# Power_Supply_for_CPU_Blocks.net
KiCad netlist of a schematic drawn in Altium Designer
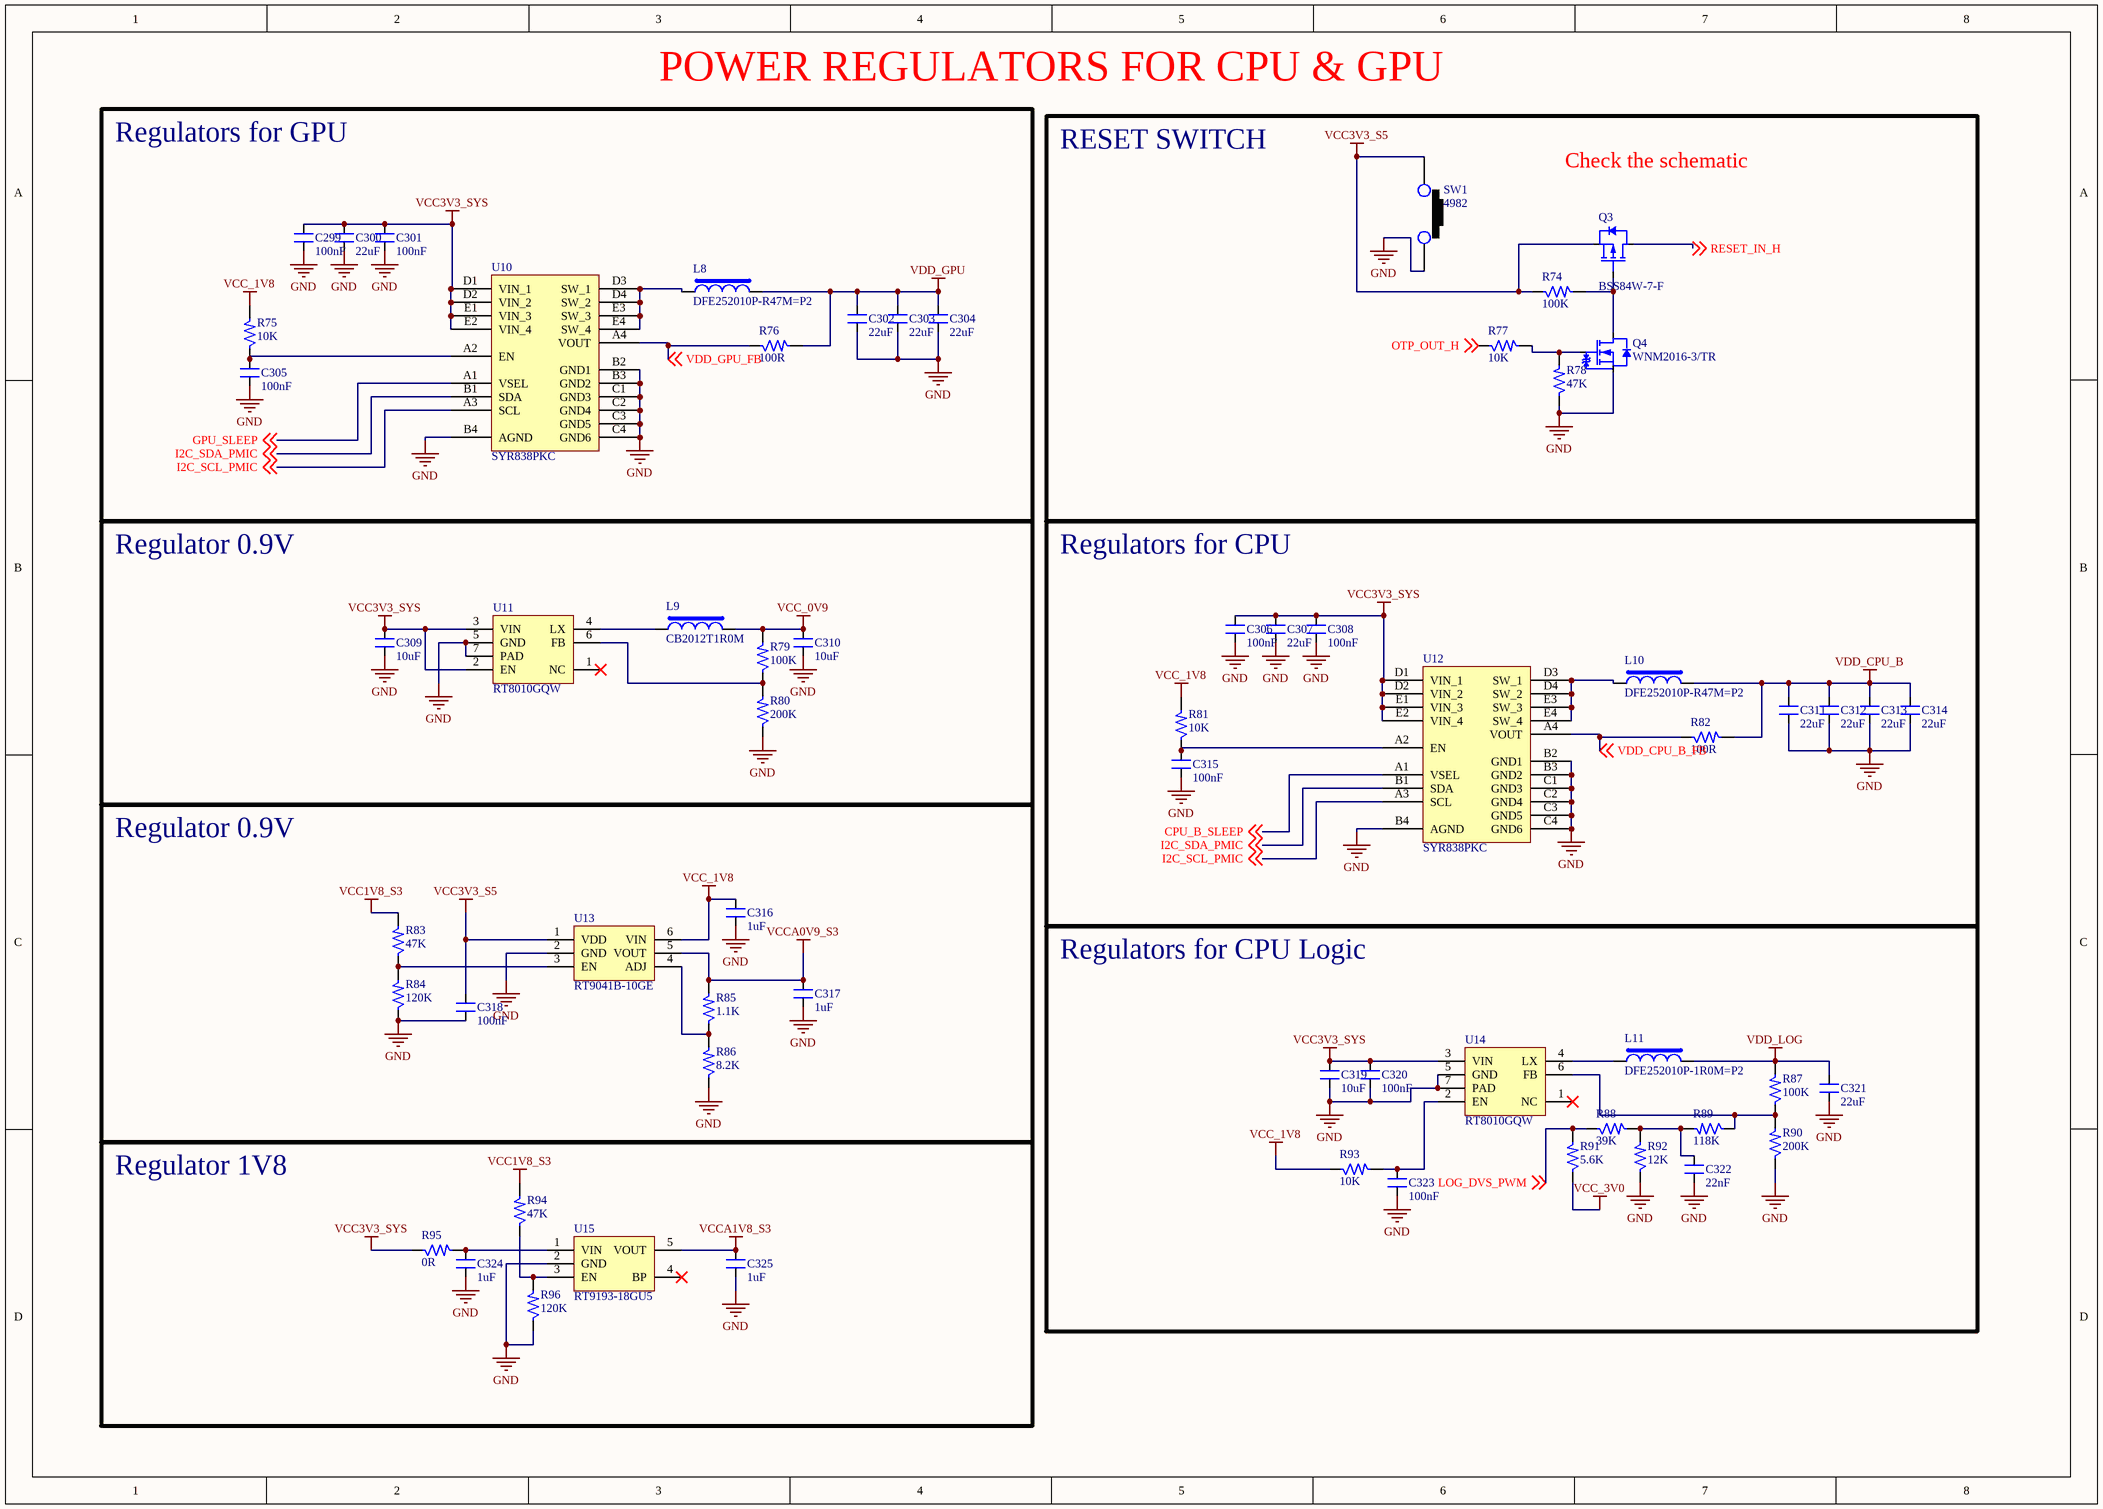
[diagram p0: Power Supply for CPU Blocks.SchDoc]

(export (version "E")
  (design (tool "Eeschema 10.0.6"))
  (components
    (comp (ref "C299")
      (value "100nF")
      (footprint "CAP_0603")
      (description "0.1µF ±10% 10V Ceramic Capacitor X7R 0603 (1608 Metric)")
      (fields
        (field (name "MANUFACTURER") "Yageo")
        (field (name "MANUFACTURER PART NUMBER") "CC0603KRX7R6BB104")
      )
      (libsource (lib "RK3399 _Module_Schlib") (part "CAP_100nF-10V-5%-0603"))
    )
    (comp (ref "C300")
      (value "22uF")
      (footprint "CAP_0603")
      (description "22µF ±20% 10V Ceramic Capacitor X5R 0603 (1608 Metric)")
      (fields
        (field (name "MANUFACTURER") "Murata Electronics")
        (field (name "MANUFACTURER PART NUMBER") "GRM188R61A226ME15D")
      )
      (libsource (lib "RK3399 _Module_Schlib") (part "CAP_22uF-10V-20%-0603"))
    )
    (comp (ref "C301")
      (value "100nF")
      (footprint "CAP_0603")
      (description "0.1µF ±10% 10V Ceramic Capacitor X7R 0603 (1608 Metric)")
      (fields
        (field (name "MANUFACTURER") "Yageo")
        (field (name "MANUFACTURER PART NUMBER") "CC0603KRX7R6BB104")
      )
      (libsource (lib "RK3399 _Module_Schlib") (part "CAP_100nF-10V-5%-0603"))
    )
    (comp (ref "C302")
      (value "22uF")
      (footprint "CAP_0805")
      (description "22µF ±20% 25V Ceramic Capacitor X5R 0805 (2012 Metric)")
      (fields
        (field (name "MANUFACTURER") "Murata Electronics")
        (field (name "MANUFACTURER PART NUMBER") "GRM21BR61E226ME44K")
      )
      (libsource (lib "RK3399 _Module_Schlib") (part "CAP_22uF-25V-20%-0805"))
    )
    (comp (ref "C303")
      (value "22uF")
      (footprint "CAP_0805")
      (description "22µF ±20% 25V Ceramic Capacitor X5R 0805 (2012 Metric)")
      (fields
        (field (name "MANUFACTURER") "Murata Electronics")
        (field (name "MANUFACTURER PART NUMBER") "GRM21BR61E226ME44K")
      )
      (libsource (lib "RK3399 _Module_Schlib") (part "CAP_22uF-25V-20%-0805"))
    )
    (comp (ref "C304")
      (value "22uF")
      (footprint "CAP_0805")
      (description "22µF ±20% 25V Ceramic Capacitor X5R 0805 (2012 Metric)")
      (fields
        (field (name "MANUFACTURER") "Murata Electronics")
        (field (name "MANUFACTURER PART NUMBER") "GRM21BR61E226ME44K")
      )
      (libsource (lib "RK3399 _Module_Schlib") (part "CAP_22uF-25V-20%-0805"))
    )
    (comp (ref "C305")
      (value "100nF")
      (footprint "CAP_0603")
      (description "0.1µF ±10% 10V Ceramic Capacitor X7R 0603 (1608 Metric)")
      (fields
        (field (name "MANUFACTURER") "Yageo")
        (field (name "MANUFACTURER PART NUMBER") "CC0603KRX7R6BB104")
      )
      (libsource (lib "RK3399 _Module_Schlib") (part "CAP_100nF-10V-5%-0603"))
    )
    (comp (ref "C306")
      (value "100nF")
      (footprint "CAP_0603")
      (description "0.1µF ±10% 10V Ceramic Capacitor X7R 0603 (1608 Metric)")
      (fields
        (field (name "MANUFACTURER") "Yageo")
        (field (name "MANUFACTURER PART NUMBER") "CC0603KRX7R6BB104")
      )
      (libsource (lib "RK3399 _Module_Schlib") (part "CAP_100nF-10V-5%-0603"))
    )
    (comp (ref "C307")
      (value "22uF")
      (footprint "CAP_0603")
      (description "22µF ±20% 10V Ceramic Capacitor X5R 0603 (1608 Metric)")
      (fields
        (field (name "MANUFACTURER") "Murata Electronics")
        (field (name "MANUFACTURER PART NUMBER") "GRM188R61A226ME15D")
      )
      (libsource (lib "RK3399 _Module_Schlib") (part "CAP_22uF-10V-20%-0603"))
    )
    (comp (ref "C308")
      (value "100nF")
      (footprint "CAP_0603")
      (description "0.1µF ±10% 10V Ceramic Capacitor X7R 0603 (1608 Metric)")
      (fields
        (field (name "MANUFACTURER") "Yageo")
        (field (name "MANUFACTURER PART NUMBER") "CC0603KRX7R6BB104")
      )
      (libsource (lib "RK3399 _Module_Schlib") (part "CAP_100nF-10V-5%-0603"))
    )
    (comp (ref "C309")
      (value "10uF")
      (footprint "CAP_0603")
      (description "10µF ±10% 10V Ceramic Capacitor X5R 0603 (1608 Metric)")
      (fields
        (field (name "MANUFACTURER PART NUMBER") "GRM188R61A106KE69J")
        (field (name "MANUFACTURER") "Murata Electronics")
      )
      (libsource (lib "RK3399 _Module_Schlib") (part "CAP_10uF-10V-10%-0603"))
    )
    (comp (ref "C310")
      (value "10uF")
      (footprint "CAP_0603")
      (description "10µF ±10% 10V Ceramic Capacitor X5R 0603 (1608 Metric)")
      (fields
        (field (name "MANUFACTURER PART NUMBER") "GRM188R61A106KE69J")
        (field (name "MANUFACTURER") "Murata Electronics")
      )
      (libsource (lib "RK3399 _Module_Schlib") (part "CAP_10uF-10V-10%-0603"))
    )
    (comp (ref "C311")
      (value "22uF")
      (footprint "CAP_0805")
      (description "22µF ±20% 25V Ceramic Capacitor X5R 0805 (2012 Metric)")
      (fields
        (field (name "MANUFACTURER") "Murata Electronics")
        (field (name "MANUFACTURER PART NUMBER") "GRM21BR61E226ME44K")
      )
      (libsource (lib "RK3399 _Module_Schlib") (part "CAP_22uF-25V-20%-0805"))
    )
    (comp (ref "C312")
      (value "22uF")
      (footprint "CAP_0805")
      (description "22µF ±20% 25V Ceramic Capacitor X5R 0805 (2012 Metric)")
      (fields
        (field (name "MANUFACTURER") "Murata Electronics")
        (field (name "MANUFACTURER PART NUMBER") "GRM21BR61E226ME44K")
      )
      (libsource (lib "RK3399 _Module_Schlib") (part "CAP_22uF-25V-20%-0805"))
    )
    (comp (ref "C313")
      (value "22uF")
      (footprint "CAP_0805")
      (description "22µF ±20% 25V Ceramic Capacitor X5R 0805 (2012 Metric)")
      (fields
        (field (name "MANUFACTURER") "Murata Electronics")
        (field (name "MANUFACTURER PART NUMBER") "GRM21BR61E226ME44K")
      )
      (libsource (lib "RK3399 _Module_Schlib") (part "CAP_22uF-25V-20%-0805"))
    )
    (comp (ref "C314")
      (value "22uF")
      (footprint "CAP_0805")
      (description "22µF ±20% 25V Ceramic Capacitor X5R 0805 (2012 Metric)")
      (fields
        (field (name "MANUFACTURER") "Murata Electronics")
        (field (name "MANUFACTURER PART NUMBER") "GRM21BR61E226ME44K")
      )
      (libsource (lib "RK3399 _Module_Schlib") (part "CAP_22uF-25V-20%-0805"))
    )
    (comp (ref "C315")
      (value "100nF")
      (footprint "CAP_0603")
      (description "0.1µF ±10% 10V Ceramic Capacitor X7R 0603 (1608 Metric)")
      (fields
        (field (name "MANUFACTURER") "Yageo")
        (field (name "MANUFACTURER PART NUMBER") "CC0603KRX7R6BB104")
      )
      (libsource (lib "RK3399 _Module_Schlib") (part "CAP_100nF-10V-5%-0603"))
    )
    (comp (ref "C316")
      (value "1uF")
      (footprint "CAP_0603")
      (description "1µF ±10% 10V Ceramic Capacitor X5R 0603 (1608 Metric)")
      (fields
        (field (name "MANUFACTURER") "Samsung Electro-Mechanics")
        (field (name "MANUFACTURER PART NUMBER") "CL10A105KP8NNNC")
      )
      (libsource (lib "RK3399 _Module_Schlib") (part "CAP_1uF-10V-5%-0603"))
    )
    (comp (ref "C317")
      (value "1uF")
      (footprint "CAP_0603")
      (description "1µF ±10% 10V Ceramic Capacitor X5R 0603 (1608 Metric)")
      (fields
        (field (name "MANUFACTURER") "Samsung Electro-Mechanics")
        (field (name "MANUFACTURER PART NUMBER") "CL10A105KP8NNNC")
      )
      (libsource (lib "RK3399 _Module_Schlib") (part "CAP_1uF-10V-5%-0603"))
    )
    (comp (ref "C318")
      (value "100nF")
      (footprint "CAP_0603")
      (description "0.1µF ±10% 10V Ceramic Capacitor X7R 0603 (1608 Metric)")
      (fields
        (field (name "MANUFACTURER") "Yageo")
        (field (name "MANUFACTURER PART NUMBER") "CC0603KRX7R6BB104")
      )
      (libsource (lib "RK3399 _Module_Schlib") (part "CAP_100nF-10V-5%-0603"))
    )
    (comp (ref "C319")
      (value "10uF")
      (footprint "CAP_0603")
      (description "10µF ±10% 10V Ceramic Capacitor X5R 0603 (1608 Metric)")
      (fields
        (field (name "MANUFACTURER PART NUMBER") "GRM188R61A106KE69J")
        (field (name "MANUFACTURER") "Murata Electronics")
      )
      (libsource (lib "RK3399 _Module_Schlib") (part "CAP_10uF-10V-10%-0603"))
    )
    (comp (ref "C320")
      (value "100nF")
      (footprint "CAP_0603")
      (description "0.1µF ±10% 10V Ceramic Capacitor X7R 0603 (1608 Metric)")
      (fields
        (field (name "MANUFACTURER") "Yageo")
        (field (name "MANUFACTURER PART NUMBER") "CC0603KRX7R6BB104")
      )
      (libsource (lib "RK3399 _Module_Schlib") (part "CAP_100nF-10V-5%-0603"))
    )
    (comp (ref "C321")
      (value "22uF")
      (footprint "CAP_0603")
      (description "22µF ±20% 10V Ceramic Capacitor X5R 0603 (1608 Metric)")
      (fields
        (field (name "MANUFACTURER") "Murata Electronics")
        (field (name "MANUFACTURER PART NUMBER") "GRM188R61A226ME15D")
      )
      (libsource (lib "RK3399 _Module_Schlib") (part "CAP_22uF-10V-20%-0603"))
    )
    (comp (ref "C322")
      (value "22nF")
      (footprint "CAP_0603")
      (description "0.022µF ±10% 10V Ceramic Capacitor X7R 0603 (1608 Metric)")
      (fields
        (field (name "MANUFACTURER PART NUMBER") "LMF107B7223KAHT")
        (field (name "MANUFACTURER") "Taiyo Yuden")
      )
      (libsource (lib "RK3399 _Module_Schlib") (part "CAP_22nF-10V-10%-0603"))
    )
    (comp (ref "C323")
      (value "100nF")
      (footprint "CAP_0603")
      (description "0.1µF ±10% 10V Ceramic Capacitor X7R 0603 (1608 Metric)")
      (fields
        (field (name "MANUFACTURER") "Yageo")
        (field (name "MANUFACTURER PART NUMBER") "CC0603KRX7R6BB104")
      )
      (libsource (lib "RK3399 _Module_Schlib") (part "CAP_100nF-10V-5%-0603"))
    )
    (comp (ref "C324")
      (value "1uF")
      (footprint "CAP_0603")
      (description "1µF ±10% 10V Ceramic Capacitor X5R 0603 (1608 Metric)")
      (fields
        (field (name "MANUFACTURER") "Samsung Electro-Mechanics")
        (field (name "MANUFACTURER PART NUMBER") "CL10A105KP8NNNC")
      )
      (libsource (lib "RK3399 _Module_Schlib") (part "CAP_1uF-10V-5%-0603"))
    )
    (comp (ref "C325")
      (value "1uF")
      (footprint "CAP_0603")
      (description "1µF ±10% 10V Ceramic Capacitor X5R 0603 (1608 Metric)")
      (fields
        (field (name "MANUFACTURER") "Samsung Electro-Mechanics")
        (field (name "MANUFACTURER PART NUMBER") "CL10A105KP8NNNC")
      )
      (libsource (lib "RK3399 _Module_Schlib") (part "CAP_1uF-10V-5%-0603"))
    )
    (comp (ref "L8")
      (value "DFE252010P-R47M=P2")
      (footprint "IND_1008")
      (description "470nH Shielded Wirewound Inductor 5A 35mOhm Max 1008 (2520 Metric)")
      (fields (field (name "MANUFACTURER") "Murata Electronics"))
      (libsource (lib "RK3399 _Module_Schlib") (part "IND_470nH-5A-20%-1008"))
    )
    (comp (ref "L9")
      (value "CB2012T1R0M")
      (footprint "IND_0805")
      (description "1uH ±20% 500mA 150mΩ 0805 Inductors (SMD) RoHS")
      (fields (field (name "MANUFACTURER") "Taiyo Yuden"))
      (libsource (lib "RK3399 _Module_Schlib") (part "IND_1uF-0.5A-20%-0805"))
    )
    (comp (ref "L10")
      (value "DFE252010P-R47M=P2")
      (footprint "IND_1008")
      (description "470nH Shielded Wirewound Inductor 5A 35mOhm Max 1008 (2520 Metric)")
      (fields (field (name "MANUFACTURER") "Murata Electronics"))
      (libsource (lib "RK3399 _Module_Schlib") (part "IND_470nH-5A-20%-1008"))
    )
    (comp (ref "L11")
      (value "DFE252010P-1R0M=P2")
      (footprint "IND_1008")
      (description "1µH Shielded Wirewound Inductor 3.8A 54mOhm Max 1008 (2520 Metric)")
      (fields (field (name "MANUFACTURER") "Murata Electronics"))
      (libsource (lib "RK3399 _Module_Schlib") (part "IND_1uH-3.8A-20%-1008"))
    )
    (comp (ref "Q3")
      (value "BSS84W-7-F")
      (footprint "SOT-323-3")
      (description "P-Channel 50V 130mA (Ta) 200mW (Ta) Surface Mount SOT-323")
      (fields (field (name "MANUFACTURER") "Diodes Incorporated"))
      (libsource (lib "RK3399 _Module_Schlib") (part "MOSFET-P_50V-130mA-SOT-323"))
    )
    (comp (ref "Q4")
      (value "WNM2016-3/TR")
      (footprint "SOT 23-3")
      (description "N Channel 20V 2.9A 1V @ 250uA 47mΩ @ 3.6A,4.5V 700mW SOT-23(SOT-23-3) MOSFET RoHS")
      (fields (field (name "MANUFACTURER") "WILLSEMI(Will Semicon)"))
      (libsource (lib "EsteemPCB_COB_Course_intlib") (part "MOSFET-N_20V-2.9A-SOT-23"))
    )
    (comp (ref "R74")
      (value "100K")
      (footprint "RES_0603")
      (description "100 kOhms ±1% 0.1W, 1/10W Chip Resistor 0603 (1608 Metric) Automotive AEC-Q200 Thick Film")
      (fields
        (field (name "MANUFACTURER") "tackpole Electronics Inc")
        (field (name "MANUFACTURER PART NUMBER") "RMCF0603FT100K")
      )
      (libsource (lib "RK3399 _Module_Schlib") (part "RES_100K-0.1W-1%-0603"))
    )
    (comp (ref "R75")
      (value "10K")
      (footprint "RES_0603")
      (description "10 kOhms ±1% 0.1W, 1/10W Chip Resistor 0603 (1608 Metric) Thick Film")
      (fields
        (field (name "MANUFACTURER") "Yageo")
        (field (name "MANUFACTURER PART NUMBER") "RC0603FR-0710KL")
      )
      (libsource (lib "RK3399 _Module_Schlib") (part "RES_10K-0.1W-1%-0603"))
    )
    (comp (ref "R76")
      (value "100R")
      (footprint "RES_0603")
      (description "100 Ohms ±1% 0.1W, 1/10W Chip Resistor 0603 (1608 Metric) Thick Film")
      (fields
        (field (name "MANUFACTURER") "Yageo")
        (field (name "MANUFACTURER PART NUMBER") "RC0603FR-07100RL")
      )
      (libsource (lib "RK3399 _Module_Schlib") (part "RES_100R-0.1W-1%-0603"))
    )
    (comp (ref "R77")
      (value "10K")
      (footprint "RES_0603")
      (description "10 kOhms ±1% 0.1W, 1/10W Chip Resistor 0603 (1608 Metric) Thick Film")
      (fields
        (field (name "MANUFACTURER") "Yageo")
        (field (name "MANUFACTURER PART NUMBER") "RC0603FR-0710KL")
      )
      (libsource (lib "RK3399 _Module_Schlib") (part "RES_10K-0.1W-1%-0603"))
    )
    (comp (ref "R78")
      (value "47K")
      (footprint "RES_0603")
      (description "47 kOhms ±1% 0.1W, 1/10W Chip Resistor 0603 (1608 Metric) Thick Film")
      (fields
        (field (name "MANUFACTURER") "Yageo")
        (field (name "MANUFACTURER PART NUMBER") "RC0603FR-0747KL")
      )
      (libsource (lib "RK3399 _Module_Schlib") (part "RES_47K-0.1W-1%-0603"))
    )
    (comp (ref "R79")
      (value "100K")
      (footprint "RES_0603")
      (description "100 kOhms ±1% 0.1W, 1/10W Chip Resistor 0603 (1608 Metric) Automotive AEC-Q200 Thick Film")
      (fields
        (field (name "MANUFACTURER") "tackpole Electronics Inc")
        (field (name "MANUFACTURER PART NUMBER") "RMCF0603FT100K")
      )
      (libsource (lib "RK3399 _Module_Schlib") (part "RES_100K-0.1W-1%-0603"))
    )
    (comp (ref "R80")
      (value "200K")
      (footprint "RES_0603")
      (description "200 kOhms ±1% 0.1W, 1/10W Chip Resistor 0603 (1608 Metric) Thick Film")
      (fields
        (field (name "MANUFACTURER") "Yageo")
        (field (name "MANUFACTURER PART NUMBER") "RC0603FR-07200KL")
      )
      (libsource (lib "RK3399 _Module_Schlib") (part "RES_200K-0.1W-1%-0603"))
    )
    (comp (ref "R81")
      (value "10K")
      (footprint "RES_0603")
      (description "10 kOhms ±1% 0.1W, 1/10W Chip Resistor 0603 (1608 Metric) Thick Film")
      (fields
        (field (name "MANUFACTURER") "Yageo")
        (field (name "MANUFACTURER PART NUMBER") "RC0603FR-0710KL")
      )
      (libsource (lib "RK3399 _Module_Schlib") (part "RES_10K-0.1W-1%-0603"))
    )
    (comp (ref "R82")
      (value "100R")
      (footprint "RES_0603")
      (description "100 Ohms ±1% 0.1W, 1/10W Chip Resistor 0603 (1608 Metric) Thick Film")
      (fields
        (field (name "MANUFACTURER") "Yageo")
        (field (name "MANUFACTURER PART NUMBER") "RC0603FR-07100RL")
      )
      (libsource (lib "RK3399 _Module_Schlib") (part "RES_100R-0.1W-1%-0603"))
    )
    (comp (ref "R83")
      (value "47K")
      (footprint "RES_0603")
      (description "47 kOhms ±1% 0.1W, 1/10W Chip Resistor 0603 (1608 Metric) Thick Film")
      (fields
        (field (name "MANUFACTURER") "Yageo")
        (field (name "MANUFACTURER PART NUMBER") "RC0603FR-0747KL")
      )
      (libsource (lib "RK3399 _Module_Schlib") (part "RES_47K-0.1W-1%-0603"))
    )
    (comp (ref "R84")
      (value "120K")
      (footprint "RES_0603")
      (description "120 kOhms ±1% 0.1W, 1/10W Chip Resistor 0603 (1608 Metric) Thin Film")
      (fields
        (field (name "MANUFACTURER") "Yageo")
        (field (name "MANUFACTURER PART NUMBER") "RT0603FRE07120KL")
      )
      (libsource (lib "RK3399 _Module_Schlib") (part "RES_120K-0.1W-1%-0603"))
    )
    (comp (ref "R85")
      (value "1.1K")
      (footprint "RES_0603")
      (description "47 kOhms ±1% 0.1W, 1/10W Chip Resistor 0603 (1608 Metric) Thick Film")
      (fields
        (field (name "MANUFACTURER") "Yageo")
        (field (name "MANUFACTURER PART NUMBER") "RC0603FR-0747KL")
      )
      (libsource (lib "RK3399 _Module_Schlib") (part "RES_1.1K-0.1W-1%-0603"))
    )
    (comp (ref "R86")
      (value "8.2K")
      (footprint "RES_0603")
      (description "8.2 kOhms ±1% 0.1W, 1/10W Chip Resistor 0603 (1608 Metric) Automotive AEC-Q200 Thick Film")
      (fields
        (field (name "MANUFACTURER") "Stackpole Electronics Inc")
        (field (name "MANUFACTURER PART NUMBER") "RMCF0603FT8K20")
      )
      (libsource (lib "RK3399 _Module_Schlib") (part "RES_8.2K-0.1W-1%-0603"))
    )
    (comp (ref "R87")
      (value "100K")
      (footprint "RES_0603")
      (description "100 kOhms ±1% 0.1W, 1/10W Chip Resistor 0603 (1608 Metric) Automotive AEC-Q200 Thick Film")
      (fields
        (field (name "MANUFACTURER") "tackpole Electronics Inc")
        (field (name "MANUFACTURER PART NUMBER") "RMCF0603FT100K")
      )
      (libsource (lib "RK3399 _Module_Schlib") (part "RES_100K-0.1W-1%-0603"))
    )
    (comp (ref "R88")
      (value "39K")
      (footprint "RES_0603")
      (fields
        (field (name "MANUFACTURER") "TE Connectivity Passive Product")
        (field (name "MANUFACTURER PART NUMBER") "CRGCQ0603F39K")
      )
      (libsource (lib "RK3399 _Module_Schlib") (part "RES_39K-0.1W-1%-0603"))
    )
    (comp (ref "R89")
      (value "118K")
      (footprint "RES_0603")
      (description "118 kOhms ±1% 0.1W, 1/10W Chip Resistor 0603 (1608 Metric) Automotive AEC-Q200 Thick Film")
      (fields
        (field (name "MANUFACTURER") "Stackpole Electronics Inc")
        (field (name "MANUAFCTURER PART NUMBER") "RMCF0603FT118K")
      )
      (libsource (lib "RK3399 _Module_Schlib") (part "RES_118K-0.1W-1%-0603"))
    )
    (comp (ref "R90")
      (value "200K")
      (footprint "RES_0603")
      (description "200 kOhms ±1% 0.1W, 1/10W Chip Resistor 0603 (1608 Metric) Thick Film")
      (fields
        (field (name "MANUFACTURER") "Yageo")
        (field (name "MANUFACTURER PART NUMBER") "RC0603FR-07200KL")
      )
      (libsource (lib "RK3399 _Module_Schlib") (part "RES_200K-0.1W-1%-0603"))
    )
    (comp (ref "R91")
      (value "5.6K")
      (footprint "RES_0603")
      (fields
        (field (name "MANUFACTURER") "TE Connectivity Passive Product")
        (field (name "MANUFACTURER PART NUMBER") "CRGCQ0603F5K6")
      )
      (libsource (lib "RK3399 _Module_Schlib") (part "RES_5.6K-0.1W-1%-0603"))
    )
    (comp (ref "R92")
      (value "12K")
      (footprint "RES_0603")
      (description "12 kOhms ±1% 0.1W, 1/10W Chip Resistor 0603 (1608 Metric) Thick Film")
      (fields
        (field (name "MANUFACTURER") "TE Connectivity Passive Product")
        (field (name "MANUFACTURER PART NUMBER") "CRG0603F12K")
      )
      (libsource (lib "RK3399 _Module_Schlib") (part "RES_12K-0.1W-1%-0603"))
    )
    (comp (ref "R93")
      (value "10K")
      (footprint "RES_0603")
      (description "10 kOhms ±1% 0.1W, 1/10W Chip Resistor 0603 (1608 Metric) Thick Film")
      (fields
        (field (name "MANUFACTURER") "Yageo")
        (field (name "MANUFACTURER PART NUMBER") "RC0603FR-0710KL")
      )
      (libsource (lib "RK3399 _Module_Schlib") (part "RES_10K-0.1W-1%-0603"))
    )
    (comp (ref "R94")
      (value "47K")
      (footprint "RES_0603")
      (description "47 kOhms ±1% 0.1W, 1/10W Chip Resistor 0603 (1608 Metric) Thick Film")
      (fields
        (field (name "MANUFACTURER") "Yageo")
        (field (name "MANUFACTURER PART NUMBER") "RC0603FR-0747KL")
      )
      (libsource (lib "RK3399 _Module_Schlib") (part "RES_47K-0.1W-1%-0603"))
    )
    (comp (ref "R95")
      (value "0R")
      (footprint "RES_0603")
      (description "0 Ohms Jumper 0.1W, 1/10W Chip Resistor 0603 (1608 Metric) Thick Film")
      (fields
        (field (name "MANUFACTURER") "Yageo")
        (field (name "MANUFACTURER PART NUMBER") "RC0603JR-070RL")
      )
      (libsource (lib "RK3399 _Module_Schlib") (part "RES_0R-0.1W-1%-0603"))
    )
    (comp (ref "R96")
      (value "120K")
      (footprint "RES_0603")
      (description "120 kOhms ±1% 0.1W, 1/10W Chip Resistor 0603 (1608 Metric) Thin Film")
      (fields
        (field (name "MANUFACTURER") "Yageo")
        (field (name "MANUFACTURER PART NUMBER") "RT0603FRE07120KL")
      )
      (libsource (lib "RK3399 _Module_Schlib") (part "RES_120K-0.1W-1%-0603"))
    )
    (comp (ref "SW1")
      (value "4982")
      (footprint "SW_177_39.3X77.7_SMD")
      (description "Tactile Switch 3x4x2mm SMD 2-Pin")
      (fields (field (name "MANUFACTURER") "NA"))
      (libsource (lib "EsteemPCB_COB_Course_intlib") (part "SW1_4982"))
    )
    (comp (ref "U10")
      (value "SYR838PKC")
      (footprint "CSP20_15.7_100x84_SMD")
      (description "Step-Down Positive Programmable 1 6A 2.4MHz CSP1.56*1.96-20 DC-DC Converters RoHS")
      (fields (field (name "MANUFACTURER") "Silergy Corp"))
      (libsource (lib "RK3399 _Module_Schlib") (part "IC_SYR838PKC"))
    )
    (comp (ref "U11")
      (value "RT8010GQW")
      (footprint "WDFN-6_26_133X100_SMD")
      (description "Buck Switching Regulator IC Positive Adjustable 0.6V 1 Output 1A 6-WDFN Exposed Pad")
      (fields (field (name "MANUFACTURER") "Richtek USA Inc."))
      (libsource (lib "RK3399 _Module_Schlib") (part "REG-ADJ_5.5V-5.5V-1A-6-WDFN"))
    )
    (comp (ref "U12")
      (value "SYR838PKC")
      (footprint "CSP20_15.7_100x84_SMD")
      (description "Step-Down Positive Programmable 1 6A 2.4MHz CSP1.56*1.96-20 DC-DC Converters RoHS")
      (fields (field (name "MANUFACTURER") "Silergy Corp"))
      (libsource (lib "RK3399 _Module_Schlib") (part "IC_SYR838PKC"))
    )
    (comp (ref "U13")
      (value "RT9041B-10GE")
      (footprint "SOT23-6")
      (description "Linear Voltage Regulator IC 1 Output 500mA SOT-23-6")
      (fields (field (name "MANUFACTURER") "Richtek USA Inc."))
      (libsource (lib "RK3399 _Module_Schlib") (part "REG-ADJ_5.5V-2.5V-0.5A-SOT-23-6"))
    )
    (comp (ref "U14")
      (value "RT8010GQW")
      (footprint "WDFN-6_26_133X100_SMD")
      (description "Buck Switching Regulator IC Positive Adjustable 0.6V 1 Output 1A 6-WDFN Exposed Pad")
      (fields (field (name "MANUFACTURER") "Richtek USA Inc."))
      (libsource (lib "RK3399 _Module_Schlib") (part "REG-ADJ_5.5V-5.5V-1A-6-WDFN"))
    )
    (comp (ref "U15")
      (value "RT9193-18GU5")
      (footprint "SOT23-5")
      (description "Linear Voltage Regulator IC 1 Output 300mA SC-70-5")
      (fields (field (name "MANUFACTURER") "Richtek USA Inc."))
      (libsource (lib "RK3399 _Module_Schlib") (part "REG_1.8V-300mA-5.5V-SC70-5"))
    )
  )
  (nets
    (net (code "1") (name "CPU_B_SLEEP") (class "Default")
      (node (ref "U12") (pin "A1") (pinfunction "VSEL_A1") (pintype "passive"))
    )
    (net (code "2") (name "GND") (class "Default")
      (node (ref "C299") (pin "1") (pinfunction "1_1") (pintype "passive"))
      (node (ref "C300") (pin "1") (pinfunction "1_1") (pintype "passive"))
      (node (ref "C301") (pin "1") (pinfunction "1_1") (pintype "passive"))
      (node (ref "C302") (pin "1") (pinfunction "1_1") (pintype "passive"))
      (node (ref "C303") (pin "1") (pinfunction "1_1") (pintype "passive"))
      (node (ref "C304") (pin "1") (pinfunction "1_1") (pintype "passive"))
      (node (ref "C305") (pin "1") (pinfunction "1_1") (pintype "passive"))
      (node (ref "C306") (pin "1") (pinfunction "1_1") (pintype "passive"))
      (node (ref "C307") (pin "1") (pinfunction "1_1") (pintype "passive"))
      (node (ref "C308") (pin "1") (pinfunction "1_1") (pintype "passive"))
      (node (ref "C309") (pin "1") (pinfunction "1_1") (pintype "passive"))
      (node (ref "C310") (pin "1") (pinfunction "1_1") (pintype "passive"))
      (node (ref "C311") (pin "1") (pinfunction "1_1") (pintype "passive"))
      (node (ref "C312") (pin "1") (pinfunction "1_1") (pintype "passive"))
      (node (ref "C313") (pin "1") (pinfunction "1_1") (pintype "passive"))
      (node (ref "C314") (pin "1") (pinfunction "1_1") (pintype "passive"))
      (node (ref "C315") (pin "1") (pinfunction "1_1") (pintype "passive"))
      (node (ref "C316") (pin "1") (pinfunction "1_1") (pintype "passive"))
      (node (ref "C317") (pin "1") (pinfunction "1_1") (pintype "passive"))
      (node (ref "C318") (pin "1") (pinfunction "1_1") (pintype "passive"))
      (node (ref "C319") (pin "1") (pinfunction "1_1") (pintype "passive"))
      (node (ref "C320") (pin "1") (pinfunction "1_1") (pintype "passive"))
      (node (ref "C321") (pin "1") (pinfunction "1_1") (pintype "passive"))
      (node (ref "C322") (pin "1") (pinfunction "1_1") (pintype "passive"))
      (node (ref "C323") (pin "1") (pinfunction "1_1") (pintype "passive"))
      (node (ref "C324") (pin "1") (pinfunction "1_1") (pintype "passive"))
      (node (ref "C325") (pin "1") (pinfunction "1_1") (pintype "passive"))
      (node (ref "Q4") (pin "2") (pinfunction "S_2") (pintype "passive"))
      (node (ref "R78") (pin "1") (pinfunction "1_1") (pintype "passive"))
      (node (ref "R80") (pin "1") (pinfunction "1_1") (pintype "passive"))
      (node (ref "R84") (pin "1") (pinfunction "1_1") (pintype "passive"))
      (node (ref "R86") (pin "1") (pinfunction "1_1") (pintype "passive"))
      (node (ref "R90") (pin "1") (pinfunction "1_1") (pintype "passive"))
      (node (ref "R92") (pin "1") (pinfunction "1_1") (pintype "passive"))
      (node (ref "R96") (pin "1") (pinfunction "1_1") (pintype "passive"))
      (node (ref "SW1") (pin "2") (pinfunction "2_2") (pintype "passive"))
      (node (ref "U10") (pin "B2") (pinfunction "GND1_B2") (pintype "passive"))
      (node (ref "U10") (pin "B3") (pinfunction "GND2_B3") (pintype "passive"))
      (node (ref "U10") (pin "B4") (pinfunction "AGND_B4") (pintype "passive"))
      (node (ref "U10") (pin "C1") (pinfunction "GND3_C1") (pintype "passive"))
      (node (ref "U10") (pin "C2") (pinfunction "GND4_C2") (pintype "passive"))
      (node (ref "U10") (pin "C3") (pinfunction "GND5_C3") (pintype "passive"))
      (node (ref "U10") (pin "C4") (pinfunction "GND6_C4") (pintype "passive"))
      (node (ref "U11") (pin "5") (pinfunction "GND_5") (pintype "passive"))
      (node (ref "U11") (pin "7") (pinfunction "PAD_7") (pintype "passive"))
      (node (ref "U12") (pin "B2") (pinfunction "GND1_B2") (pintype "passive"))
      (node (ref "U12") (pin "B3") (pinfunction "GND2_B3") (pintype "passive"))
      (node (ref "U12") (pin "B4") (pinfunction "AGND_B4") (pintype "passive"))
      (node (ref "U12") (pin "C1") (pinfunction "GND3_C1") (pintype "passive"))
      (node (ref "U12") (pin "C2") (pinfunction "GND4_C2") (pintype "passive"))
      (node (ref "U12") (pin "C3") (pinfunction "GND5_C3") (pintype "passive"))
      (node (ref "U12") (pin "C4") (pinfunction "GND6_C4") (pintype "passive"))
      (node (ref "U13") (pin "2") (pinfunction "GND_2") (pintype "passive"))
      (node (ref "U14") (pin "5") (pinfunction "GND_5") (pintype "passive"))
      (node (ref "U14") (pin "7") (pinfunction "PAD_7") (pintype "passive"))
      (node (ref "U15") (pin "2") (pinfunction "GND_2") (pintype "passive"))
    )
    (net (code "3") (name "GPU_SLEEP") (class "Default")
      (node (ref "U10") (pin "A1") (pinfunction "VSEL_A1") (pintype "passive"))
    )
    (net (code "4") (name "I2C_SCL_PMIC") (class "Default")
      (node (ref "U10") (pin "A3") (pinfunction "SCL_A3") (pintype "passive"))
      (node (ref "U12") (pin "A3") (pinfunction "SCL_A3") (pintype "passive"))
    )
    (net (code "5") (name "I2C_SDA_PMIC") (class "Default")
      (node (ref "U10") (pin "B1") (pinfunction "SDA_B1") (pintype "passive"))
      (node (ref "U12") (pin "B1") (pinfunction "SDA_B1") (pintype "passive"))
    )
    (net (code "6") (name "LOG_DVS_PWM") (class "Default")
      (node (ref "R88") (pin "1") (pinfunction "1_1") (pintype "passive"))
      (node (ref "R91") (pin "2") (pinfunction "2_2") (pintype "passive"))
    )
    (net (code "7") (name "Net-(C322-Pad2)") (class "Default")
      (node (ref "C322") (pin "2") (pinfunction "2_2") (pintype "passive"))
      (node (ref "R88") (pin "2") (pinfunction "2_2") (pintype "passive"))
      (node (ref "R89") (pin "2") (pinfunction "2_2") (pintype "passive"))
      (node (ref "R92") (pin "2") (pinfunction "2_2") (pintype "passive"))
    )
    (net (code "8") (name "Net-(Q3-G)") (class "Default")
      (node (ref "Q3") (pin "1") (pinfunction "G_1") (pintype "passive"))
      (node (ref "Q4") (pin "3") (pinfunction "D_3") (pintype "passive"))
      (node (ref "R74") (pin "2") (pinfunction "2_2") (pintype "passive"))
    )
    (net (code "9") (name "Net-(Q4-G)") (class "Default")
      (node (ref "Q4") (pin "1") (pinfunction "G_1") (pintype "passive"))
      (node (ref "R77") (pin "2") (pinfunction "2_2") (pintype "passive"))
      (node (ref "R78") (pin "2") (pinfunction "2_2") (pintype "passive"))
    )
    (net (code "10") (name "Net-(U10-EN)") (class "Default")
      (node (ref "C305") (pin "2") (pinfunction "2_2") (pintype "passive"))
      (node (ref "R75") (pin "1") (pinfunction "1_1") (pintype "passive"))
      (node (ref "U10") (pin "A2") (pinfunction "EN_A2") (pintype "passive"))
    )
    (net (code "11") (name "Net-(U10-SW_1)") (class "Default")
      (node (ref "L8") (pin "1") (pinfunction "1_1") (pintype "passive"))
      (node (ref "U10") (pin "D3") (pinfunction "SW_1_D3") (pintype "passive"))
      (node (ref "U10") (pin "D4") (pinfunction "SW_2_D4") (pintype "passive"))
      (node (ref "U10") (pin "E3") (pinfunction "SW_3_E3") (pintype "passive"))
      (node (ref "U10") (pin "E4") (pinfunction "SW_4_E4") (pintype "passive"))
    )
    (net (code "12") (name "Net-(U11-FB)") (class "Default")
      (node (ref "R79") (pin "1") (pinfunction "1_1") (pintype "passive"))
      (node (ref "R80") (pin "2") (pinfunction "2_2") (pintype "passive"))
      (node (ref "U11") (pin "6") (pinfunction "FB_6") (pintype "passive"))
    )
    (net (code "13") (name "Net-(U11-LX)") (class "Default")
      (node (ref "L9") (pin "1") (pinfunction "1_1") (pintype "passive"))
      (node (ref "U11") (pin "4") (pinfunction "LX_4") (pintype "passive"))
    )
    (net (code "14") (name "Net-(U12-EN)") (class "Default")
      (node (ref "C315") (pin "2") (pinfunction "2_2") (pintype "passive"))
      (node (ref "R81") (pin "1") (pinfunction "1_1") (pintype "passive"))
      (node (ref "U12") (pin "A2") (pinfunction "EN_A2") (pintype "passive"))
    )
    (net (code "15") (name "Net-(U12-SW_1)") (class "Default")
      (node (ref "L10") (pin "1") (pinfunction "1_1") (pintype "passive"))
      (node (ref "U12") (pin "D3") (pinfunction "SW_1_D3") (pintype "passive"))
      (node (ref "U12") (pin "D4") (pinfunction "SW_2_D4") (pintype "passive"))
      (node (ref "U12") (pin "E3") (pinfunction "SW_3_E3") (pintype "passive"))
      (node (ref "U12") (pin "E4") (pinfunction "SW_4_E4") (pintype "passive"))
    )
    (net (code "16") (name "Net-(U13-ADJ)") (class "Default")
      (node (ref "R85") (pin "1") (pinfunction "1_1") (pintype "passive"))
      (node (ref "R86") (pin "2") (pinfunction "2_2") (pintype "passive"))
      (node (ref "U13") (pin "4") (pinfunction "ADJ_4") (pintype "passive"))
    )
    (net (code "17") (name "Net-(U13-EN)") (class "Default")
      (node (ref "R83") (pin "1") (pinfunction "1_1") (pintype "passive"))
      (node (ref "R84") (pin "2") (pinfunction "2_2") (pintype "passive"))
      (node (ref "U13") (pin "3") (pinfunction "EN_3") (pintype "passive"))
    )
    (net (code "18") (name "Net-(U14-EN)") (class "Default")
      (node (ref "C323") (pin "2") (pinfunction "2_2") (pintype "passive"))
      (node (ref "R93") (pin "2") (pinfunction "2_2") (pintype "passive"))
      (node (ref "U14") (pin "2") (pinfunction "EN_2") (pintype "passive"))
    )
    (net (code "19") (name "Net-(U14-FB)") (class "Default")
      (node (ref "R87") (pin "1") (pinfunction "1_1") (pintype "passive"))
      (node (ref "R89") (pin "1") (pinfunction "1_1") (pintype "passive"))
      (node (ref "R90") (pin "2") (pinfunction "2_2") (pintype "passive"))
      (node (ref "U14") (pin "6") (pinfunction "FB_6") (pintype "passive"))
    )
    (net (code "20") (name "Net-(U14-LX)") (class "Default")
      (node (ref "L11") (pin "1") (pinfunction "1_1") (pintype "passive"))
      (node (ref "U14") (pin "4") (pinfunction "LX_4") (pintype "passive"))
    )
    (net (code "21") (name "Net-(U15-EN)") (class "Default")
      (node (ref "R94") (pin "1") (pinfunction "1_1") (pintype "passive"))
      (node (ref "R96") (pin "2") (pinfunction "2_2") (pintype "passive"))
      (node (ref "U15") (pin "3") (pinfunction "EN_3") (pintype "passive"))
    )
    (net (code "22") (name "Net-(U15-VIN)") (class "Default")
      (node (ref "C324") (pin "2") (pinfunction "2_2") (pintype "passive"))
      (node (ref "R95") (pin "2") (pinfunction "2_2") (pintype "passive"))
      (node (ref "U15") (pin "1") (pinfunction "VIN_1") (pintype "passive"))
    )
    (net (code "23") (name "OTP_OUT_H") (class "Default")
      (node (ref "R77") (pin "1") (pinfunction "1_1") (pintype "passive"))
    )
    (net (code "24") (name "RESET_IN_H") (class "Default")
      (node (ref "Q3") (pin "3") (pinfunction "D_3") (pintype "passive"))
    )
    (net (code "25") (name "VCC1V8_S3") (class "Default")
      (node (ref "R83") (pin "2") (pinfunction "2_2") (pintype "passive"))
      (node (ref "R94") (pin "2") (pinfunction "2_2") (pintype "passive"))
    )
    (net (code "26") (name "VCC3V3_S5") (class "Default")
      (node (ref "C318") (pin "2") (pinfunction "2_2") (pintype "passive"))
      (node (ref "Q3") (pin "2") (pinfunction "S_2") (pintype "passive"))
      (node (ref "R74") (pin "1") (pinfunction "1_1") (pintype "passive"))
      (node (ref "SW1") (pin "1") (pinfunction "1_1") (pintype "passive"))
      (node (ref "U13") (pin "1") (pinfunction "VDD_1") (pintype "passive"))
    )
    (net (code "27") (name "VCC3V3_SYS") (class "Default")
      (node (ref "C299") (pin "2") (pinfunction "2_2") (pintype "passive"))
      (node (ref "C300") (pin "2") (pinfunction "2_2") (pintype "passive"))
      (node (ref "C301") (pin "2") (pinfunction "2_2") (pintype "passive"))
      (node (ref "C306") (pin "2") (pinfunction "2_2") (pintype "passive"))
      (node (ref "C307") (pin "2") (pinfunction "2_2") (pintype "passive"))
      (node (ref "C308") (pin "2") (pinfunction "2_2") (pintype "passive"))
      (node (ref "C309") (pin "2") (pinfunction "2_2") (pintype "passive"))
      (node (ref "C319") (pin "2") (pinfunction "2_2") (pintype "passive"))
      (node (ref "C320") (pin "2") (pinfunction "2_2") (pintype "passive"))
      (node (ref "R95") (pin "1") (pinfunction "1_1") (pintype "passive"))
      (node (ref "U10") (pin "D1") (pinfunction "VIN_1_D1") (pintype "passive"))
      (node (ref "U10") (pin "D2") (pinfunction "VIN_2_D2") (pintype "passive"))
      (node (ref "U10") (pin "E1") (pinfunction "VIN_3_E1") (pintype "passive"))
      (node (ref "U10") (pin "E2") (pinfunction "VIN_4_E2") (pintype "passive"))
      (node (ref "U11") (pin "2") (pinfunction "EN_2") (pintype "passive"))
      (node (ref "U11") (pin "3") (pinfunction "VIN_3") (pintype "passive"))
      (node (ref "U12") (pin "D1") (pinfunction "VIN_1_D1") (pintype "passive"))
      (node (ref "U12") (pin "D2") (pinfunction "VIN_2_D2") (pintype "passive"))
      (node (ref "U12") (pin "E1") (pinfunction "VIN_3_E1") (pintype "passive"))
      (node (ref "U12") (pin "E2") (pinfunction "VIN_4_E2") (pintype "passive"))
      (node (ref "U14") (pin "3") (pinfunction "VIN_3") (pintype "passive"))
    )
    (net (code "28") (name "VCCA0V9_S3") (class "Default")
      (node (ref "C317") (pin "2") (pinfunction "2_2") (pintype "passive"))
      (node (ref "R85") (pin "2") (pinfunction "2_2") (pintype "passive"))
      (node (ref "U13") (pin "5") (pinfunction "VOUT_5") (pintype "passive"))
    )
    (net (code "29") (name "VCCA1V8_S3") (class "Default")
      (node (ref "C325") (pin "2") (pinfunction "2_2") (pintype "passive"))
      (node (ref "U15") (pin "5") (pinfunction "VOUT_5") (pintype "passive"))
    )
    (net (code "30") (name "VCC_0V9") (class "Default")
      (node (ref "C310") (pin "2") (pinfunction "2_2") (pintype "passive"))
      (node (ref "L9") (pin "2") (pinfunction "2_2") (pintype "passive"))
      (node (ref "R79") (pin "2") (pinfunction "2_2") (pintype "passive"))
    )
    (net (code "31") (name "VCC_1V8") (class "Default")
      (node (ref "C316") (pin "2") (pinfunction "2_2") (pintype "passive"))
      (node (ref "R75") (pin "2") (pinfunction "2_2") (pintype "passive"))
      (node (ref "R81") (pin "2") (pinfunction "2_2") (pintype "passive"))
      (node (ref "R93") (pin "1") (pinfunction "1_1") (pintype "passive"))
      (node (ref "U13") (pin "6") (pinfunction "VIN_6") (pintype "passive"))
    )
    (net (code "32") (name "VCC_3V0") (class "Default")
      (node (ref "R91") (pin "1") (pinfunction "1_1") (pintype "passive"))
    )
    (net (code "33") (name "VDD_CPU_B") (class "Default")
      (node (ref "C311") (pin "2") (pinfunction "2_2") (pintype "passive"))
      (node (ref "C312") (pin "2") (pinfunction "2_2") (pintype "passive"))
      (node (ref "C313") (pin "2") (pinfunction "2_2") (pintype "passive"))
      (node (ref "C314") (pin "2") (pinfunction "2_2") (pintype "passive"))
      (node (ref "L10") (pin "2") (pinfunction "2_2") (pintype "passive"))
      (node (ref "R82") (pin "2") (pinfunction "2_2") (pintype "passive"))
    )
    (net (code "34") (name "VDD_CPU_B_FB") (class "Default")
      (node (ref "R82") (pin "1") (pinfunction "1_1") (pintype "passive"))
      (node (ref "U12") (pin "A4") (pinfunction "VOUT_A4") (pintype "passive"))
    )
    (net (code "35") (name "VDD_GPU") (class "Default")
      (node (ref "C302") (pin "2") (pinfunction "2_2") (pintype "passive"))
      (node (ref "C303") (pin "2") (pinfunction "2_2") (pintype "passive"))
      (node (ref "C304") (pin "2") (pinfunction "2_2") (pintype "passive"))
      (node (ref "L8") (pin "2") (pinfunction "2_2") (pintype "passive"))
      (node (ref "R76") (pin "2") (pinfunction "2_2") (pintype "passive"))
    )
    (net (code "36") (name "VDD_GPU_FB") (class "Default")
      (node (ref "R76") (pin "1") (pinfunction "1_1") (pintype "passive"))
      (node (ref "U10") (pin "A4") (pinfunction "VOUT_A4") (pintype "passive"))
    )
    (net (code "37") (name "VDD_LOG") (class "Default")
      (node (ref "C321") (pin "2") (pinfunction "2_2") (pintype "passive"))
      (node (ref "L11") (pin "2") (pinfunction "2_2") (pintype "passive"))
      (node (ref "R87") (pin "2") (pinfunction "2_2") (pintype "passive"))
    )
    (net (code "38") (name "unconnected-(U11-NC-Pad1)") (class "Default")
      (node (ref "U11") (pin "1") (pinfunction "NC_1") (pintype "passive+no_connect"))
    )
    (net (code "39") (name "unconnected-(U14-NC-Pad1)") (class "Default")
      (node (ref "U14") (pin "1") (pinfunction "NC_1") (pintype "passive+no_connect"))
    )
    (net (code "40") (name "unconnected-(U15-BP-Pad4)") (class "Default")
      (node (ref "U15") (pin "4") (pinfunction "BP_4") (pintype "passive+no_connect"))
    )
  )
)
